# Sheet2.net
KiCad netlist of a schematic drawn in Altium Designer
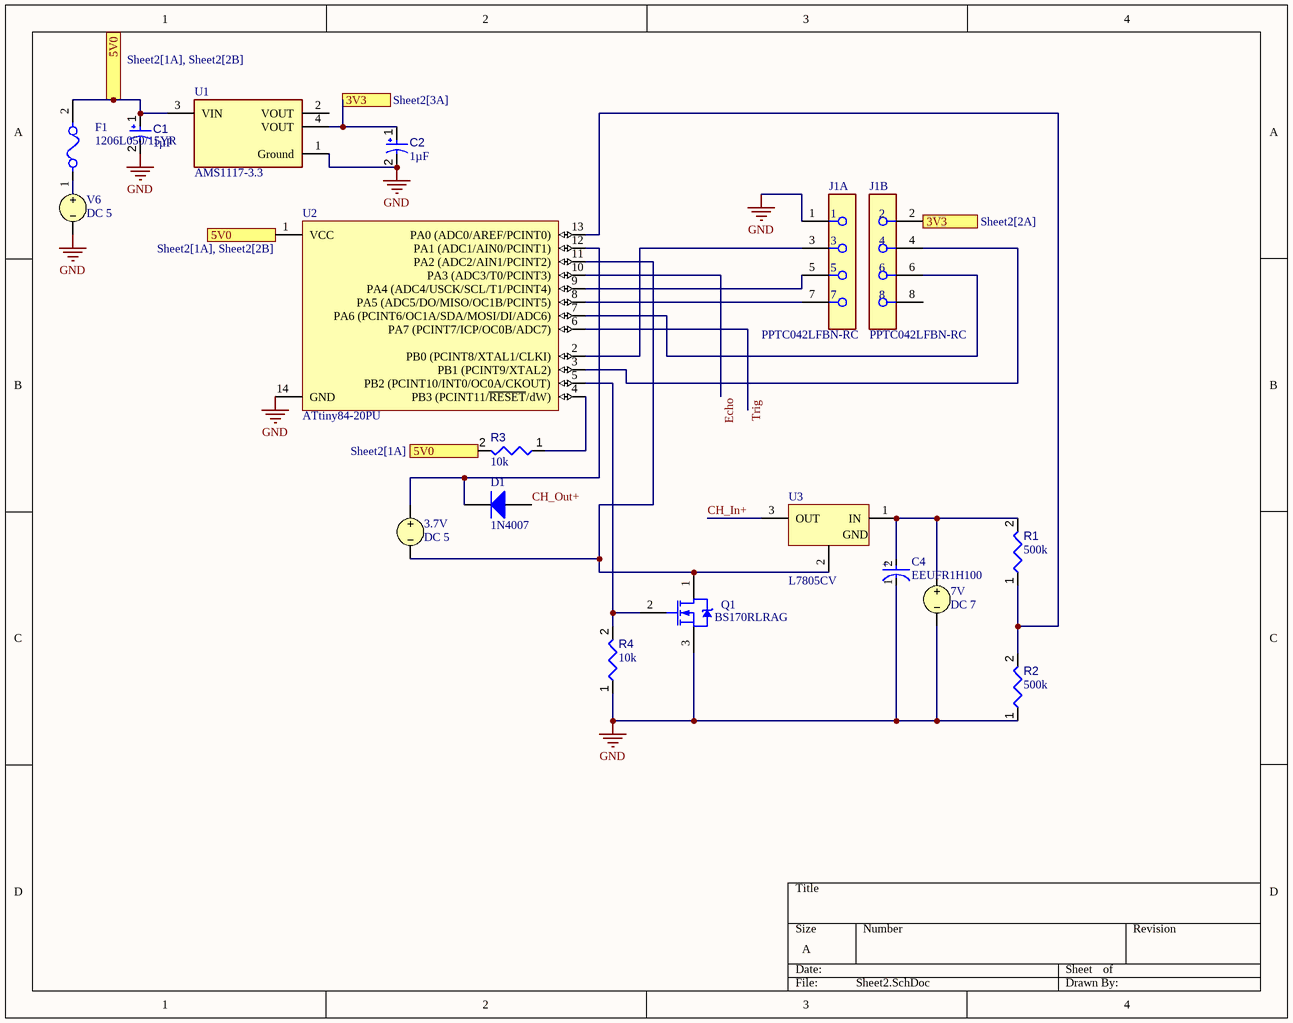
[diagram p0: Sheet2.SchDoc]

(export (version "E")
  (design (tool "Eeschema 10.0.6"))
  (components
    (comp (ref "3.7V")
      (value "DC 5")
      (description "Voltage Source")
      (fields (field (name "PUBLISHER") "Altium Limited"))
      (libsource (lib "Simulation Generic Components") (part "VSRC"))
    )
    (comp (ref "7V")
      (value "DC 7")
      (description "Voltage Source")
      (fields (field (name "PUBLISHER") "Altium Limited"))
      (libsource (lib "Simulation Generic Components") (part "VSRC"))
    )
    (comp (ref "C1")
      (value "1µF")
      (footprint "CAPPR55-200-1100X500X1200")
      (description "Aluminum Electrolytic Capacitor, 1 uF, +/- 20%, 50 V, -55 to 105 degC, 2-Pin THD, RoHS, Bulk")
      (fields (field (name "TOLERANCE") "20%") (field (name "MANUFACTURER") "Panasonic"))
      (libsource (lib "Adheesha") (part "CAP-P-2"))
    )
    (comp (ref "C2")
      (value "1µF")
      (footprint "CAPPR55-200-1100X500X1200")
      (description "Aluminum Electrolytic Capacitor, 1 uF, +/- 20%, 50 V, -55 to 105 degC, 2-Pin THD, RoHS, Bulk")
      (fields (field (name "TOLERANCE") "20%") (field (name "MANUFACTURER") "Panasonic"))
      (libsource (lib "Adheesha") (part "CAP-P-2"))
    )
    (comp (ref "C4")
      (value "EEUFR1H100")
      (footprint "FP-RAD-TH-D_5_0_5-L_11_1-MFG")
      (description "Aluminum Electrolytic Capacitors (Radial Lead Type) 10uF ±20% 50V")
      (fields (field (name "TOLERANCE") "20%") (field (name "VOLTAGE") "50V"))
      (libsource (lib "Altium Content Vault") (part "a00bbbee19879c290e62620ae7e47b1"))
    )
    (comp (ref "D1")
      (value "1N4007")
      (footprint "FAIR-DO-41-2")
      (description "General Purpose Rectifier, 1.1 V, 1.0 A, -55 to 175 degC, 2-Pin DO-41, RoHS, Tape and Reel")
      (fields (field (name "MANUFACTURER") "Fairchild"))
      (libsource (lib "Adheesha") (part "KESE-D_K1A2-2"))
    )
    (comp (ref "F1")
      (value "1206L050/15YR")
      (footprint "FP-1206L-MFG")
      (description "PTC RESET FUSE 15V 500MA 1206")
      (fields
        (field (name "MANUFACTURER") "Littelfuse Inc")
        (field (name "OCTOPART") "https://octopart.com/1206l050%2F15yr-littelfuse-673645")
      )
      (libsource (lib "Altium Content Vault") (part "5bcf9b9f640e542cf0359d10258e979"))
    )
    (comp (ref "J1")
      (value "PPTC042LFBN-RC")
      (footprint "FP-PPTC042LFBN-RC-MFG")
      (description "CONN HDR 8POS 0.1 TIN PCB")
      (fields
        (field (name "OCTOPART") "https://octopart.com/pptc042lfbn-rc-sullins-271088")
        (field (name "MANUFACTURER") "Sullins")
      )
      (libsource (lib "Altium Content Vault") (part "f7953d7cc9e5fc6ef8e06ef09a26288"))
    )
    (comp (ref "Q1")
      (value "BS170RLRAG")
      (footprint "ONSC-TO-92-3-29-11_AM_BL")
      (description "Small Signal MOSFET, 500 mA, 60 V, N-Channel, 3-Pin TO-92, Pb-Free, Tape and Reel")
      (fields (field (name "MANUFACTURER") "On Semiconductor"))
      (libsource (lib "Altium Content Vault") (part "ONSC-NMOS-D1G2S3-3"))
    )
    (comp (ref "R1")
      (value "500k")
      (footprint "RESA60-630X240")
      (description "Axial Resistor, 1 KOhm, +/- 1%, 250 mW, -55 to 155 degC, 2-Pin THD, RoHS, Bulk")
      (fields (field (name "TOLERANCE") "1%") (field (name "POWER") "250mW"))
      (libsource (lib "Adheesha") (part "RES-2"))
    )
    (comp (ref "R2")
      (value "500k")
      (footprint "RESA60-630X240")
      (description "Axial Resistor, 1 KOhm, +/- 1%, 250 mW, -55 to 155 degC, 2-Pin THD, RoHS, Bulk")
      (fields (field (name "TOLERANCE") "1%") (field (name "POWER") "250mW"))
      (libsource (lib "Adheesha") (part "RES-2"))
    )
    (comp (ref "R3")
      (value "10k")
      (footprint "RESA60-630X240")
      (description "Axial Resistor, 1 KOhm, +/- 1%, 250 mW, -55 to 155 degC, 2-Pin THD, RoHS, Bulk")
      (fields (field (name "TOLERANCE") "1%") (field (name "POWER") "250mW"))
      (libsource (lib "Adheesha") (part "RES-2"))
    )
    (comp (ref "R4")
      (value "10k")
      (footprint "RESA60-630X240")
      (description "Axial Resistor, 1 KOhm, +/- 1%, 250 mW, -55 to 155 degC, 2-Pin THD, RoHS, Bulk")
      (fields (field (name "TOLERANCE") "1%") (field (name "POWER") "250mW"))
      (libsource (lib "Adheesha") (part "RES-2"))
    )
    (comp (ref "U1")
      (value "AMS1117-3.3")
      (footprint "FP-AMS1117-IPC_C")
      (description "LDO Voltage Regulators 1A, 3.3V")
      (fields
        (field (name "OCTOPART") "https://octopart.com/ams1117-3.3-advanced+monolithic+systems-25899300")
        (field (name "MANUFACTURER") "Advanced Monolithic Systems")
      )
      (libsource (lib "Altium Content Vault") (part "8bdbb5f8e77002000e30dd2845d0354"))
    )
    (comp (ref "U2")
      (value "ATtiny84-20PU")
      (footprint "14P3")
      (libsource (lib "Altium Content Vault") (part "MC-8B-ATTINY24V-IL14"))
    )
    (comp (ref "U3")
      (value "L7805CV")
      (footprint "TO220")
      (description "Positive Voltage Regulator, 5V, 3-Pin TO-220")
      (libsource (lib "Altium Content Vault") (part "PM-REG-L4940-SIL3"))
    )
    (comp (ref "V6")
      (value "DC 5")
      (description "Voltage Source")
      (fields (field (name "PUBLISHER") "Altium Limited"))
      (libsource (lib "Simulation Generic Components") (part "VSRC"))
    )
  )
  (nets
    (net (code "1") (name "/3V3") (class "Default")
      (node (ref "C2") (pin "1") (pinfunction "1_1") (pintype "passive"))
      (node (ref "J1") (pin "2") (pinfunction "2_2") (pintype "passive"))
      (node (ref "U1") (pin "4") (pinfunction "VOUT_4") (pintype "passive"))
    )
    (net (code "2") (name "/5V0") (class "Default")
      (node (ref "C1") (pin "1") (pinfunction "1_1") (pintype "passive"))
      (node (ref "F1") (pin "2") (pinfunction "2_2") (pintype "passive"))
      (node (ref "R3") (pin "2") (pinfunction "2_2") (pintype "passive"))
      (node (ref "U1") (pin "3") (pinfunction "VIN_3") (pintype "power_in"))
      (node (ref "U2") (pin "1") (pinfunction "VCC_1") (pintype "power_in"))
    )
    (net (code "3") (name "/CH_In+") (class "Default")
      (node (ref "U3") (pin "3") (pinfunction "OUT_3") (pintype "power_in"))
    )
    (net (code "4") (name "/CH_Out+") (class "Default")
      (node (ref "D1") (pin "2") (pinfunction "A_2") (pintype "passive"))
    )
    (net (code "5") (name "/Echo") (class "Default")
      (node (ref "U2") (pin "10") (pinfunction "PA3_(ADC3/T0/PCINT3)_10") (pintype "bidirectional"))
    )
    (net (code "6") (name "/Trig") (class "Default")
      (node (ref "U2") (pin "6") (pinfunction "PA7_(PCINT7/ICP/OC0B/ADC7)_6") (pintype "bidirectional"))
    )
    (net (code "7") (name "GND") (class "Default")
      (node (ref "7V") (pin "2") (pinfunction "2_2") (pintype "passive"))
      (node (ref "C1") (pin "2") (pinfunction "2_2") (pintype "passive"))
      (node (ref "C2") (pin "2") (pinfunction "2_2") (pintype "passive"))
      (node (ref "C4") (pin "1") (pinfunction "C_1") (pintype "passive"))
      (node (ref "J1") (pin "1") (pinfunction "1_1") (pintype "passive"))
      (node (ref "Q1") (pin "3") (pinfunction "S_3") (pintype "passive"))
      (node (ref "R2") (pin "1") (pinfunction "1_1") (pintype "passive"))
      (node (ref "R4") (pin "1") (pinfunction "1_1") (pintype "passive"))
      (node (ref "U1") (pin "1") (pinfunction "Ground_1") (pintype "power_in"))
      (node (ref "U2") (pin "14") (pinfunction "GND_14") (pintype "power_in"))
      (node (ref "V6") (pin "2") (pinfunction "2_2") (pintype "passive"))
    )
    (net (code "8") (name "Net-(C4-A)") (class "Default")
      (node (ref "7V") (pin "1") (pinfunction "1_1") (pintype "passive"))
      (node (ref "C4") (pin "2") (pinfunction "A_2") (pintype "passive"))
      (node (ref "R1") (pin "2") (pinfunction "2_2") (pintype "passive"))
      (node (ref "U3") (pin "1") (pinfunction "IN_1") (pintype "power_in"))
    )
    (net (code "9") (name "Net-(D1-K)") (class "Default")
      (node (ref "3.7V") (pin "1") (pinfunction "1_1") (pintype "passive"))
      (node (ref "D1") (pin "1") (pinfunction "K_1") (pintype "passive"))
      (node (ref "U2") (pin "12") (pinfunction "PA1_(ADC1/AIN0/PCINT1)_12") (pintype "bidirectional"))
    )
    (net (code "10") (name "Net-(F1-Pad1)") (class "Default")
      (node (ref "F1") (pin "1") (pinfunction "1_1") (pintype "passive"))
      (node (ref "V6") (pin "1") (pinfunction "1_1") (pintype "passive"))
    )
    (net (code "11") (name "Net-(Q1-D)") (class "Default")
      (node (ref "3.7V") (pin "2") (pinfunction "2_2") (pintype "passive"))
      (node (ref "Q1") (pin "1") (pinfunction "D_1") (pintype "passive"))
      (node (ref "U2") (pin "11") (pinfunction "PA2_(ADC2/AIN1/PCINT2)_11") (pintype "bidirectional"))
      (node (ref "U3") (pin "2") (pinfunction "GND_2") (pintype "power_in"))
    )
    (net (code "12") (name "Net-(Q1-G)") (class "Default")
      (node (ref "Q1") (pin "2") (pinfunction "G_2") (pintype "passive"))
      (node (ref "R4") (pin "2") (pinfunction "2_2") (pintype "passive"))
      (node (ref "U2") (pin "5") (pinfunction "PB2_(PCINT10/INT0/OC0A/CKOUT)_5") (pintype "bidirectional"))
    )
    (net (code "13") (name "Net-(U2-PA0_(ADC0{slash}AREF{slash}PCINT0))") (class "Default")
      (node (ref "R1") (pin "1") (pinfunction "1_1") (pintype "passive"))
      (node (ref "R2") (pin "2") (pinfunction "2_2") (pintype "passive"))
      (node (ref "U2") (pin "13") (pinfunction "PA0_(ADC0/AREF/PCINT0)_13") (pintype "bidirectional"))
    )
    (net (code "14") (name "Net-(U2-PA4_(ADC4{slash}USCK{slash}SCL{slash}T1{slash}PCINT4))") (class "Default")
      (node (ref "J1") (pin "5") (pinfunction "5_5") (pintype "passive"))
      (node (ref "U2") (pin "9") (pinfunction "PA4_(ADC4/USCK/SCL/T1/PCINT4)_9") (pintype "bidirectional"))
    )
    (net (code "15") (name "Net-(U2-PA5_(ADC5{slash}DO{slash}MISO{slash}OC1B{slash}PCINT5))") (class "Default")
      (node (ref "J1") (pin "7") (pinfunction "7_7") (pintype "passive"))
      (node (ref "U2") (pin "8") (pinfunction "PA5_(ADC5/DO/MISO/OC1B/PCINT5)_8") (pintype "bidirectional"))
    )
    (net (code "16") (name "Net-(U2-PA6_(PCINT6{slash}OC1A{slash}SDA{slash}MOSI{slash}DI{slash}ADC6))") (class "Default")
      (node (ref "J1") (pin "6") (pinfunction "6_6") (pintype "passive"))
      (node (ref "U2") (pin "7") (pinfunction "PA6_(PCINT6/OC1A/SDA/MOSI/DI/ADC6)_7") (pintype "bidirectional"))
    )
    (net (code "17") (name "Net-(U2-PB0_(PCINT8{slash}XTAL1{slash}CLKI))") (class "Default")
      (node (ref "J1") (pin "3") (pinfunction "3_3") (pintype "passive"))
      (node (ref "U2") (pin "2") (pinfunction "PB0_(PCINT8/XTAL1/CLKI)_2") (pintype "bidirectional"))
    )
    (net (code "18") (name "Net-(U2-PB1_(PCINT9{slash}XTAL2))") (class "Default")
      (node (ref "J1") (pin "4") (pinfunction "4_4") (pintype "passive"))
      (node (ref "U2") (pin "3") (pinfunction "PB1_(PCINT9/XTAL2)_3") (pintype "bidirectional"))
    )
    (net (code "19") (name "Net-(U2-PB3_(PCINT11{slash}~{RESET}{slash}dW))") (class "Default")
      (node (ref "R3") (pin "1") (pinfunction "1_1") (pintype "passive"))
      (node (ref "U2") (pin "4") (pinfunction "PB3_(PCINT11/~{RESET}/dW)_4") (pintype "bidirectional"))
    )
    (net (code "20") (name "unconnected-(J1-Pad8)") (class "Default")
      (node (ref "J1") (pin "8") (pinfunction "8_8") (pintype "passive"))
    )
    (net (code "21") (name "unconnected-(U1-VOUT-Pad2)") (class "Default")
      (node (ref "U1") (pin "2") (pinfunction "VOUT_2") (pintype "passive"))
    )
  )
)
